# home_info_center_esp12f.net
KiCad netlist of a schematic drawn in EAGLE
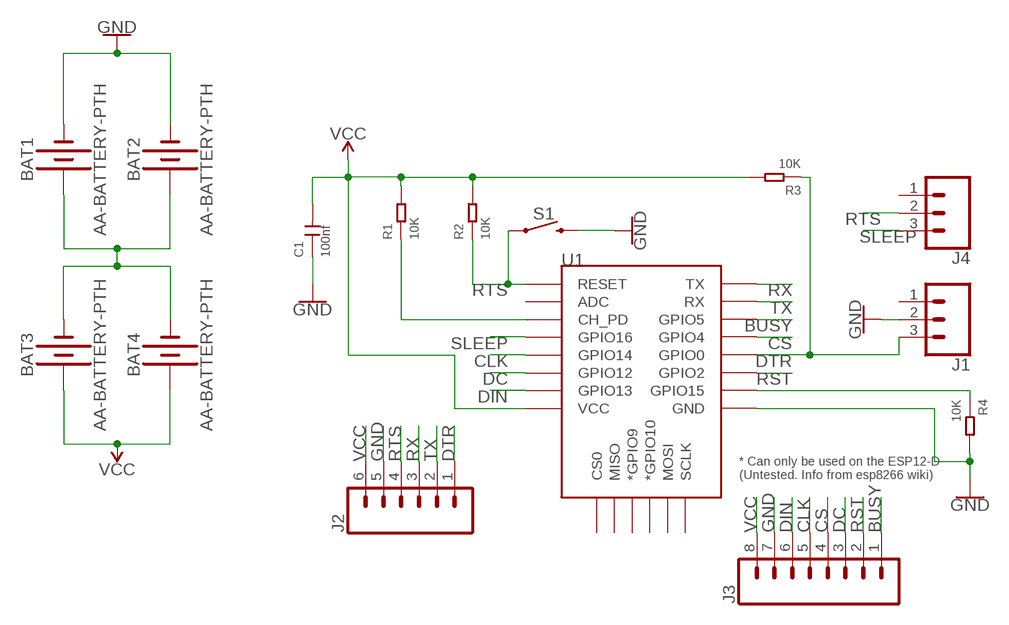
[diagram p0: schematic, sheet 1]

(export (version "E")
  (design (tool "Eeschema 10.0.6"))
  (components
    (comp (ref "BAT1")
      (value "AA-BATTERY-PTH")
      (footprint "eagle-import:AA-PCB-BATTERY")
      (libsource (lib "eagle-import") (part "AA-BATTERY-PTH"))
    )
    (comp (ref "BAT2")
      (value "AA-BATTERY-PTH")
      (footprint "eagle-import:AA-PCB-BATTERY")
      (libsource (lib "eagle-import") (part "AA-BATTERY-PTH"))
    )
    (comp (ref "BAT3")
      (value "AA-BATTERY-PTH")
      (footprint "eagle-import:AA-PCB-BATTERY")
      (libsource (lib "eagle-import") (part "AA-BATTERY-PTH"))
    )
    (comp (ref "BAT4")
      (value "AA-BATTERY-PTH")
      (footprint "eagle-import:AA-PCB-BATTERY")
      (libsource (lib "eagle-import") (part "AA-BATTERY-PTH"))
    )
    (comp (ref "C1")
      (value "100nf")
      (footprint "eagle-import:CERAMIC-2.54")
      (fields (field (name "MPN") "CC1-F5SL2A101KSPW"))
      (libsource (lib "eagle-import") (part "DIP-CERAMIC-DISC-100NF-50V-Y5V(D5.0MM)"))
    )
    (comp (ref "J1")
      (value "CONN_03")
      (footprint "eagle-import:1X03")
      (libsource (lib "eagle-import") (part "CONN_03"))
    )
    (comp (ref "J2")
      (value "CONN_06LOCK")
      (footprint "eagle-import:1X06_LOCK")
      (libsource (lib "eagle-import") (part "CONN_06LOCK"))
    )
    (comp (ref "J3")
      (value "CONN_08LOCK")
      (footprint "eagle-import:1X08_LOCK")
      (libsource (lib "eagle-import") (part "CONN_08LOCK"))
    )
    (comp (ref "J4")
      (value "CONN_03")
      (footprint "eagle-import:1X03")
      (libsource (lib "eagle-import") (part "CONN_03"))
    )
    (comp (ref "R1")
      (value "10K")
      (footprint "eagle-import:PR-D2.3XL6.5MM")
      (fields (field (name "MPN") "FHCFR-1/4W-103J"))
      (libsource (lib "eagle-import") (part "DIP-RES-10K-5%-1/4W(PR-D2.3XL6.5MM)"))
    )
    (comp (ref "R2")
      (value "10K")
      (footprint "eagle-import:PR-D2.3XL6.5MM")
      (fields (field (name "MPN") "FHCFR-1/4W-103J"))
      (libsource (lib "eagle-import") (part "DIP-RES-10K-5%-1/4W(PR-D2.3XL6.5MM)"))
    )
    (comp (ref "R3")
      (value "10K")
      (footprint "eagle-import:PR-D2.3XL6.5MM")
      (fields (field (name "MPN") "FHCFR-1/4W-103J"))
      (libsource (lib "eagle-import") (part "DIP-RES-10K-5%-1/4W(PR-D2.3XL6.5MM)"))
    )
    (comp (ref "R4")
      (value "10K")
      (footprint "eagle-import:PR-D2.3XL6.5MM")
      (fields (field (name "MPN") "FHCFR-1/4W-103J"))
      (libsource (lib "eagle-import") (part "DIP-RES-10K-5%-1/4W(PR-D2.3XL6.5MM)"))
    )
    (comp (ref "S1")
      (value "MOMENTARY-SWITCH-SPST-PTH-6.0MM-KIT")
      (footprint "eagle-import:TACTILE_SWITCH_PTH_6.0MM_KIT")
      (libsource (lib "eagle-import") (part "MOMENTARY-SWITCH-SPST-PTH-6.0MM-KIT"))
    )
    (comp (ref "U1")
      (value "ESP12ESMD")
      (footprint "eagle-import:ESP12E-SMD")
      (libsource (lib "eagle-import") (part "ESP12ESMD"))
    )
  )
  (nets
    (net (code "1") (name "/BUSY") (class "Default")
      (node (ref "J3") (pin "1") (pinfunction "1_1") (pintype "passive"))
      (node (ref "U1") (pin "GPIO5") (pinfunction "GPIO5_GPIO5") (pintype "bidirectional"))
    )
    (net (code "2") (name "/CLK") (class "Default")
      (node (ref "J3") (pin "5") (pinfunction "5_5") (pintype "passive"))
      (node (ref "U1") (pin "GPIO14") (pinfunction "GPIO14_GPIO14") (pintype "bidirectional"))
    )
    (net (code "3") (name "/CS") (class "Default")
      (node (ref "J3") (pin "4") (pinfunction "4_4") (pintype "passive"))
      (node (ref "U1") (pin "GPIO4") (pinfunction "GPIO4_GPIO4") (pintype "bidirectional"))
    )
    (net (code "4") (name "/DC") (class "Default")
      (node (ref "J3") (pin "3") (pinfunction "3_3") (pintype "passive"))
      (node (ref "U1") (pin "GPIO12") (pinfunction "GPIO12_GPIO12") (pintype "bidirectional"))
    )
    (net (code "5") (name "/DIN") (class "Default")
      (node (ref "J3") (pin "6") (pinfunction "6_6") (pintype "passive"))
      (node (ref "U1") (pin "GPIO13") (pinfunction "GPIO13_GPIO13") (pintype "bidirectional"))
    )
    (net (code "6") (name "/DTR") (class "Default")
      (node (ref "J1") (pin "3") (pinfunction "3_3") (pintype "passive"))
      (node (ref "J2") (pin "1") (pinfunction "1_1") (pintype "passive"))
      (node (ref "R3") (pin "1") (pinfunction "1_1") (pintype "passive"))
      (node (ref "U1") (pin "GPIO0") (pinfunction "GPIO0_GPIO0") (pintype "bidirectional"))
    )
    (net (code "7") (name "/RST") (class "Default")
      (node (ref "J3") (pin "2") (pinfunction "2_2") (pintype "passive"))
      (node (ref "U1") (pin "GPIO2") (pinfunction "GPIO2_GPIO2") (pintype "bidirectional"))
    )
    (net (code "8") (name "/RTS") (class "Default")
      (node (ref "J2") (pin "4") (pinfunction "4_4") (pintype "passive"))
      (node (ref "J4") (pin "2") (pinfunction "2_2") (pintype "passive"))
      (node (ref "R2") (pin "1") (pinfunction "1_1") (pintype "passive"))
      (node (ref "S1") (pin "1") (pinfunction "1_1") (pintype "passive"))
      (node (ref "U1") (pin "RESET") (pinfunction "RESET_RESET") (pintype "bidirectional"))
    )
    (net (code "9") (name "/RX") (class "Default")
      (node (ref "J2") (pin "3") (pinfunction "3_3") (pintype "passive"))
      (node (ref "U1") (pin "TXD0") (pinfunction "TX_TXD0") (pintype "bidirectional"))
    )
    (net (code "10") (name "/SLEEP") (class "Default")
      (node (ref "J4") (pin "3") (pinfunction "3_3") (pintype "passive"))
      (node (ref "U1") (pin "GPIO16") (pinfunction "GPIO16_GPIO16") (pintype "bidirectional"))
    )
    (net (code "11") (name "/TX") (class "Default")
      (node (ref "J2") (pin "2") (pinfunction "2_2") (pintype "passive"))
      (node (ref "U1") (pin "RXD0") (pinfunction "RX_RXD0") (pintype "bidirectional"))
    )
    (net (code "12") (name "GND") (class "Default")
      (node (ref "BAT1") (pin "NEG") (pinfunction "-_NEG") (pintype "power_in"))
      (node (ref "BAT2") (pin "NEG") (pinfunction "-_NEG") (pintype "power_in"))
      (node (ref "C1") (pin "1") (pinfunction "1_1") (pintype "passive"))
      (node (ref "J1") (pin "2") (pinfunction "2_2") (pintype "passive"))
      (node (ref "J2") (pin "5") (pinfunction "5_5") (pintype "passive"))
      (node (ref "J3") (pin "7") (pinfunction "7_7") (pintype "passive"))
      (node (ref "R4") (pin "2") (pinfunction "2_2") (pintype "passive"))
      (node (ref "S1") (pin "3") (pinfunction "2_3") (pintype "passive"))
      (node (ref "U1") (pin "GND") (pinfunction "GND_GND") (pintype "bidirectional"))
    )
    (net (code "13") (name "Net-(BAT1-+)") (class "Default")
      (node (ref "BAT1") (pin "POS") (pinfunction "+_POS") (pintype "power_in"))
      (node (ref "BAT2") (pin "POS") (pinfunction "+_POS") (pintype "power_in"))
      (node (ref "BAT3") (pin "NEG") (pinfunction "-_NEG") (pintype "power_in"))
      (node (ref "BAT4") (pin "NEG") (pinfunction "-_NEG") (pintype "power_in"))
    )
    (net (code "14") (name "Net-(R1-Pad1)") (class "Default")
      (node (ref "R1") (pin "1") (pinfunction "1_1") (pintype "passive"))
      (node (ref "U1") (pin "CH_PD") (pinfunction "CH_PD_CH_PD") (pintype "bidirectional"))
    )
    (net (code "15") (name "Net-(R4-Pad1)") (class "Default")
      (node (ref "R4") (pin "1") (pinfunction "1_1") (pintype "passive"))
      (node (ref "U1") (pin "GPIO15") (pinfunction "GPIO15_GPIO15") (pintype "bidirectional"))
    )
    (net (code "16") (name "VCC") (class "Default")
      (node (ref "BAT3") (pin "POS") (pinfunction "+_POS") (pintype "power_in"))
      (node (ref "BAT4") (pin "POS") (pinfunction "+_POS") (pintype "power_in"))
      (node (ref "C1") (pin "2") (pinfunction "2_2") (pintype "passive"))
      (node (ref "J2") (pin "6") (pinfunction "6_6") (pintype "passive"))
      (node (ref "J3") (pin "8") (pinfunction "8_8") (pintype "passive"))
      (node (ref "R1") (pin "2") (pinfunction "2_2") (pintype "passive"))
      (node (ref "R2") (pin "2") (pinfunction "2_2") (pintype "passive"))
      (node (ref "R3") (pin "2") (pinfunction "2_2") (pintype "passive"))
      (node (ref "U1") (pin "VCC") (pinfunction "VCC_VCC") (pintype "bidirectional"))
    )
    (net (code "17") (name "unconnected-(J1-Pad1)") (class "Default")
      (node (ref "J1") (pin "1") (pinfunction "1_1") (pintype "passive"))
    )
    (net (code "18") (name "unconnected-(J4-Pad1)") (class "Default")
      (node (ref "J4") (pin "1") (pinfunction "1_1") (pintype "passive"))
    )
    (net (code "19") (name "unconnected-(U1-*GPIO9-PadGPIO9)") (class "Default")
      (node (ref "U1") (pin "GPIO9") (pinfunction "*GPIO9_GPIO9") (pintype "bidirectional"))
    )
    (net (code "20") (name "unconnected-(U1-*GPIO10-PadGPIO10)") (class "Default")
      (node (ref "U1") (pin "GPIO10") (pinfunction "*GPIO10_GPIO10") (pintype "bidirectional"))
    )
    (net (code "21") (name "unconnected-(U1-PadADC)") (class "Default")
      (node (ref "U1") (pin "ADC") (pinfunction "ADC_ADC") (pintype "bidirectional"))
    )
    (net (code "22") (name "unconnected-(U1-PadCS0)") (class "Default")
      (node (ref "U1") (pin "CS0") (pinfunction "CS0_CS0") (pintype "bidirectional"))
    )
    (net (code "23") (name "unconnected-(U1-PadMISO)") (class "Default")
      (node (ref "U1") (pin "MISO") (pinfunction "MISO_MISO") (pintype "bidirectional"))
    )
    (net (code "24") (name "unconnected-(U1-PadMOSI)") (class "Default")
      (node (ref "U1") (pin "MOSI") (pinfunction "MOSI_MOSI") (pintype "bidirectional"))
    )
    (net (code "25") (name "unconnected-(U1-PadSCLK)") (class "Default")
      (node (ref "U1") (pin "SCLK") (pinfunction "SCLK_SCLK") (pintype "bidirectional"))
    )
  )
)
